# Wiring_Diagram.net
KiCad netlist of a schematic drawn in EAGLE
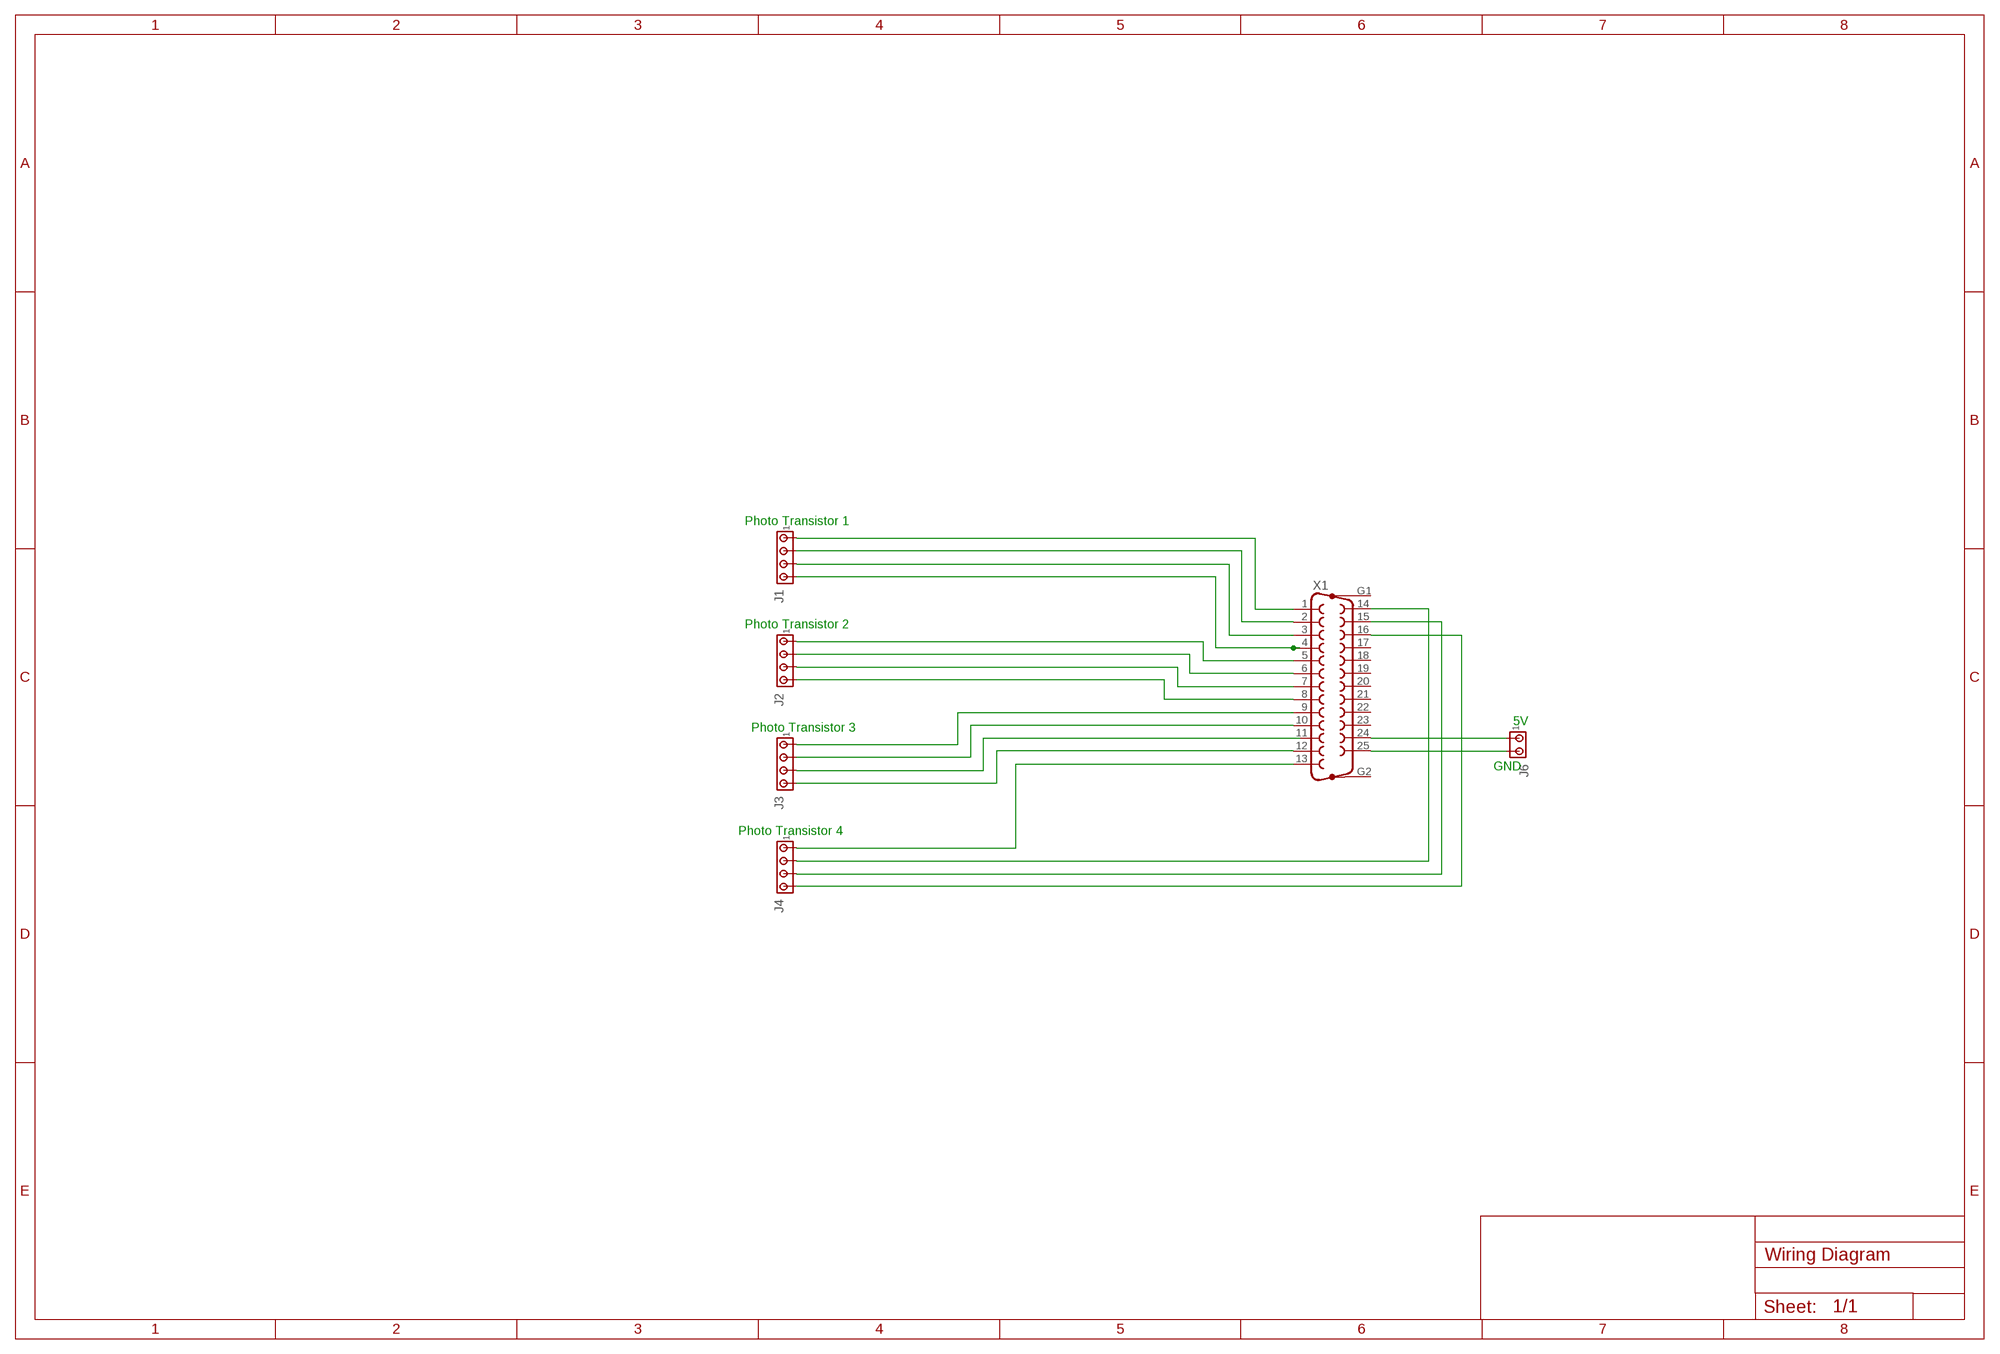
[diagram p0: schematic, sheet 1]

(export (version "E")
  (design (tool "Eeschema 10.0.6"))
  (components
    (comp (ref "J1")
      (value "MTA04-100")
      (footprint "eagle-import:10X04MTA")
      (libsource (lib "eagle-import") (part "MTA04-100"))
    )
    (comp (ref "J2")
      (value "MTA04-100")
      (footprint "eagle-import:10X04MTA")
      (libsource (lib "eagle-import") (part "MTA04-100"))
    )
    (comp (ref "J3")
      (value "MTA04-100")
      (footprint "eagle-import:10X04MTA")
      (libsource (lib "eagle-import") (part "MTA04-100"))
    )
    (comp (ref "J4")
      (value "MTA04-100")
      (footprint "eagle-import:10X04MTA")
      (libsource (lib "eagle-import") (part "MTA04-100"))
    )
    (comp (ref "J6")
      (value "MTA02-100")
      (footprint "eagle-import:10X02MTA")
      (libsource (lib "eagle-import") (part "MTA02-100"))
    )
    (comp (ref "X1")
      (value "F25HP")
      (footprint "eagle-import:F25HP")
      (libsource (lib "eagle-import") (part "F25HP"))
    )
  )
  (nets
    (net (code "1") (name "Net-(J1-Pad1)") (class "Default")
      (node (ref "J1") (pin "1") (pinfunction "1_1") (pintype "passive"))
      (node (ref "X1") (pin "1") (pinfunction "1_1") (pintype "passive"))
    )
    (net (code "2") (name "Net-(J1-Pad2)") (class "Default")
      (node (ref "J1") (pin "2") (pinfunction "2_2") (pintype "passive"))
      (node (ref "X1") (pin "2") (pinfunction "2_2") (pintype "passive"))
    )
    (net (code "3") (name "Net-(J1-Pad3)") (class "Default")
      (node (ref "J1") (pin "3") (pinfunction "3_3") (pintype "passive"))
      (node (ref "X1") (pin "3") (pinfunction "3_3") (pintype "passive"))
    )
    (net (code "4") (name "Net-(J1-Pad4)") (class "Default")
      (node (ref "J1") (pin "4") (pinfunction "4_4") (pintype "passive"))
      (node (ref "X1") (pin "4") (pinfunction "4_4") (pintype "passive"))
    )
    (net (code "5") (name "Net-(J2-Pad1)") (class "Default")
      (node (ref "J2") (pin "1") (pinfunction "1_1") (pintype "passive"))
      (node (ref "X1") (pin "5") (pinfunction "5_5") (pintype "passive"))
    )
    (net (code "6") (name "Net-(J2-Pad2)") (class "Default")
      (node (ref "J2") (pin "2") (pinfunction "2_2") (pintype "passive"))
      (node (ref "X1") (pin "6") (pinfunction "6_6") (pintype "passive"))
    )
    (net (code "7") (name "Net-(J2-Pad3)") (class "Default")
      (node (ref "J2") (pin "3") (pinfunction "3_3") (pintype "passive"))
      (node (ref "X1") (pin "7") (pinfunction "7_7") (pintype "passive"))
    )
    (net (code "8") (name "Net-(J2-Pad4)") (class "Default")
      (node (ref "J2") (pin "4") (pinfunction "4_4") (pintype "passive"))
      (node (ref "X1") (pin "8") (pinfunction "8_8") (pintype "passive"))
    )
    (net (code "9") (name "Net-(J3-Pad1)") (class "Default")
      (node (ref "J3") (pin "1") (pinfunction "1_1") (pintype "passive"))
      (node (ref "X1") (pin "9") (pinfunction "9_9") (pintype "passive"))
    )
    (net (code "10") (name "Net-(J3-Pad2)") (class "Default")
      (node (ref "J3") (pin "2") (pinfunction "2_2") (pintype "passive"))
      (node (ref "X1") (pin "10") (pinfunction "10_10") (pintype "passive"))
    )
    (net (code "11") (name "Net-(J3-Pad3)") (class "Default")
      (node (ref "J3") (pin "3") (pinfunction "3_3") (pintype "passive"))
      (node (ref "X1") (pin "11") (pinfunction "11_11") (pintype "passive"))
    )
    (net (code "12") (name "Net-(J3-Pad4)") (class "Default")
      (node (ref "J3") (pin "4") (pinfunction "4_4") (pintype "passive"))
      (node (ref "X1") (pin "12") (pinfunction "12_12") (pintype "passive"))
    )
    (net (code "13") (name "Net-(J4-Pad1)") (class "Default")
      (node (ref "J4") (pin "1") (pinfunction "1_1") (pintype "passive"))
      (node (ref "X1") (pin "13") (pinfunction "13_13") (pintype "passive"))
    )
    (net (code "14") (name "Net-(J4-Pad2)") (class "Default")
      (node (ref "J4") (pin "2") (pinfunction "2_2") (pintype "passive"))
      (node (ref "X1") (pin "14") (pinfunction "14_14") (pintype "passive"))
    )
    (net (code "15") (name "Net-(J4-Pad3)") (class "Default")
      (node (ref "J4") (pin "3") (pinfunction "3_3") (pintype "passive"))
      (node (ref "X1") (pin "15") (pinfunction "15_15") (pintype "passive"))
    )
    (net (code "16") (name "Net-(J4-Pad4)") (class "Default")
      (node (ref "J4") (pin "4") (pinfunction "4_4") (pintype "passive"))
      (node (ref "X1") (pin "16") (pinfunction "16_16") (pintype "passive"))
    )
    (net (code "17") (name "Net-(J6-Pad1)") (class "Default")
      (node (ref "J6") (pin "1") (pinfunction "1_1") (pintype "passive"))
      (node (ref "X1") (pin "24") (pinfunction "24_24") (pintype "passive"))
    )
    (net (code "18") (name "Net-(J6-Pad2)") (class "Default")
      (node (ref "J6") (pin "2") (pinfunction "2_2") (pintype "passive"))
      (node (ref "X1") (pin "25") (pinfunction "25_25") (pintype "passive"))
    )
    (net (code "19") (name "unconnected-(X1-Pad17)") (class "Default")
      (node (ref "X1") (pin "17") (pinfunction "17_17") (pintype "passive"))
    )
    (net (code "20") (name "unconnected-(X1-Pad18)") (class "Default")
      (node (ref "X1") (pin "18") (pinfunction "18_18") (pintype "passive"))
    )
    (net (code "21") (name "unconnected-(X1-Pad19)") (class "Default")
      (node (ref "X1") (pin "19") (pinfunction "19_19") (pintype "passive"))
    )
    (net (code "22") (name "unconnected-(X1-Pad20)") (class "Default")
      (node (ref "X1") (pin "20") (pinfunction "20_20") (pintype "passive"))
    )
    (net (code "23") (name "unconnected-(X1-Pad21)") (class "Default")
      (node (ref "X1") (pin "21") (pinfunction "21_21") (pintype "passive"))
    )
    (net (code "24") (name "unconnected-(X1-Pad22)") (class "Default")
      (node (ref "X1") (pin "22") (pinfunction "22_22") (pintype "passive"))
    )
    (net (code "25") (name "unconnected-(X1-Pad23)") (class "Default")
      (node (ref "X1") (pin "23") (pinfunction "23_23") (pintype "passive"))
    )
    (net (code "26") (name "unconnected-(X1-PadG1)") (class "Default")
      (node (ref "X1") (pin "G1") (pinfunction "G1_G1") (pintype "passive"))
    )
    (net (code "27") (name "unconnected-(X1-PadG2)") (class "Default")
      (node (ref "X1") (pin "G2") (pinfunction "G2_G2") (pintype "passive"))
    )
  )
)
